# I-GAUGE_5V_Rev2.net
KiCad netlist of a schematic drawn in EAGLE
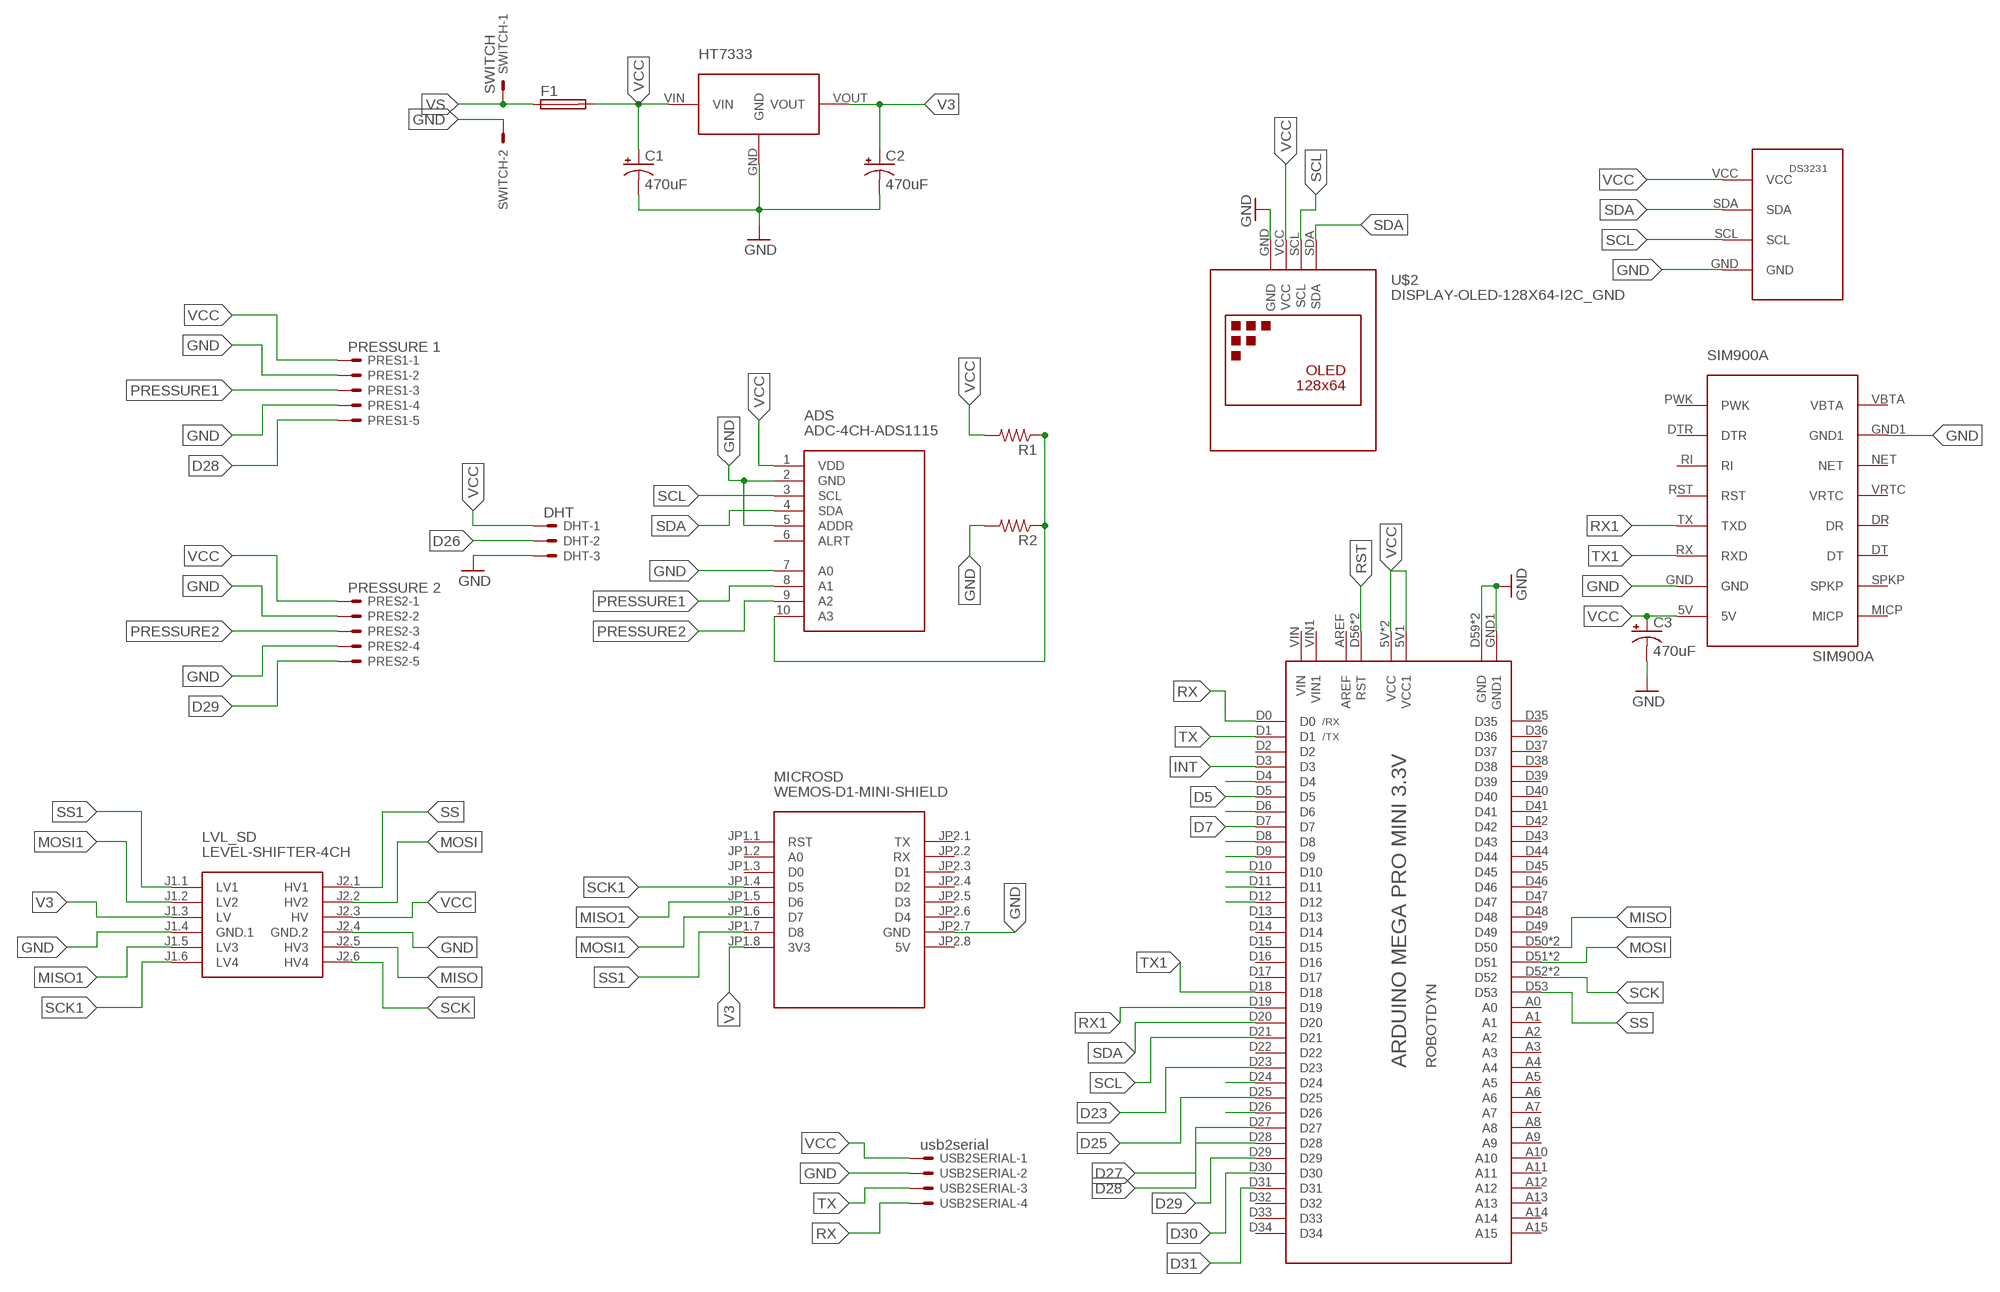
[diagram p0: schematic, sheet 1]

(export (version "E")
  (design (tool "Eeschema 10.0.6"))
  (components
    (comp (ref "ADS")
      (value "ADC-4CH-ADS1115")
      (footprint "eagle-import:ADC-4CH-ADS1115")
      (libsource (lib "eagle-import") (part "ADC-4CH-ADS1115"))
    )
    (comp (ref "C1")
      (value "470uF")
      (footprint "eagle-import:PANASONIC_G")
      (libsource (lib "eagle-import") (part "560UF-PANASONIC_G-25V-20%"))
    )
    (comp (ref "C2")
      (value "470uF")
      (footprint "eagle-import:PANASONIC_G")
      (libsource (lib "eagle-import") (part "560UF-PANASONIC_G-25V-20%"))
    )
    (comp (ref "C3")
      (value "470uF")
      (footprint "eagle-import:PANASONIC_G")
      (libsource (lib "eagle-import") (part "560UF-PANASONIC_G-25V-20%"))
    )
    (comp (ref "DHT")
      (value "DHT")
      (footprint "eagle-import:JST-XH-03-PACKAGE-ROUND-PAD")
      (libsource (lib "eagle-import") (part "JST-XH-03-PIN-ROUND-PAD"))
    )
    (comp (ref "F1")
      (value "FUSESH22,5")
      (footprint "eagle-import:SH22,5")
      (libsource (lib "eagle-import") (part "FUSESH22,5"))
    )
    (comp (ref "HT7333")
      (value "HT7333")
      (footprint "eagle-import:SOT89")
      (libsource (lib "eagle-import") (part "HT7333"))
    )
    (comp (ref "LVL_SD")
      (value "LEVEL-SHIFTER-4CH")
      (footprint "eagle-import:LEVEL-SHIFTER-4CH")
      (libsource (lib "eagle-import") (part "LEVEL-SHIFTER-4CH"))
    )
    (comp (ref "MICROSD")
      (value "WEMOS-D1-MINI-SHIELD")
      (footprint "eagle-import:WEMOS-D1-MINI-SHIELD")
      (libsource (lib "eagle-import") (part "WEMOS-D1-MINI-SHIELD"))
    )
    (comp (ref "PRES1")
      (value "PRESSURE 1")
      (footprint "eagle-import:JST-XH-05-PACKAGE-ROUND-PAD")
      (libsource (lib "eagle-import") (part "JST-XH-05-PIN-ROUND-PAD"))
    )
    (comp (ref "PRES2")
      (value "PRESSURE 2")
      (footprint "eagle-import:JST-XH-05-PACKAGE-ROUND-PAD")
      (libsource (lib "eagle-import") (part "JST-XH-05-PIN-ROUND-PAD"))
    )
    (comp (ref "R1")
      (value "R-US_M1206")
      (footprint "eagle-import:M1206")
      (libsource (lib "eagle-import") (part "R-US_M1206"))
    )
    (comp (ref "R2")
      (value "R-US_M1206")
      (footprint "eagle-import:M1206")
      (libsource (lib "eagle-import") (part "R-US_M1206"))
    )
    (comp (ref "SWITCH")
      (value "SWITCH")
      (footprint "eagle-import:JST-XH-02-PACKAGE-ROUND-PAD")
      (libsource (lib "eagle-import") (part "JST-XH-02-PIN-ROUND-PAD"))
    )
    (comp (ref "U$1")
      (value "MEGA-PRO-MINI")
      (footprint "eagle-import:MEGA-PRO-MINI")
      (libsource (lib "eagle-import") (part "MEGA-PRO-MINI"))
    )
    (comp (ref "U$2")
      (value "DISPLAY-OLED-128X64-I2C_GND")
      (footprint "eagle-import:DISPLAY-OLED-128X64-I2C_GND")
      (libsource (lib "eagle-import") (part "DISPLAY-OLED-128X64-I2C_GND"))
    )
    (comp (ref "U$5")
      (value "DS3231_RASP")
      (footprint "eagle-import:DS3231_RASP")
      (libsource (lib "eagle-import") (part "DS3231_RASP"))
    )
    (comp (ref "U$6")
      (value "SIM900A")
      (footprint "eagle-import:SIM900A")
      (libsource (lib "eagle-import") (part "SIM900A"))
    )
    (comp (ref "USB2SERIAL")
      (value "usb2serial")
      (footprint "eagle-import:JST-XH-04-PACKAGE-ROUND-PAD")
      (libsource (lib "eagle-import") (part "JST-XH-04-PIN-ROUND-PAD"))
    )
  )
  (nets
    (net (code "1") (name "/5V") (class "Default")
      (node (ref "MICROSD") (pin "JP2.8") (pinfunction "5V_JP2.8") (pintype "power_in"))
    )
    (net (code "2") (name "D5") (class "Default")
      (node (ref "U$1") (pin "D5") (pinfunction "D5_D5") (pintype "bidirectional"))
    )
    (net (code "3") (name "D7") (class "Default")
      (node (ref "U$1") (pin "D7") (pinfunction "D7_D7") (pintype "bidirectional"))
    )
    (net (code "4") (name "D23") (class "Default")
      (node (ref "U$1") (pin "D23") (pinfunction "D23_D23") (pintype "bidirectional"))
    )
    (net (code "5") (name "D25") (class "Default")
      (node (ref "U$1") (pin "D25") (pinfunction "D25_D25") (pintype "bidirectional"))
    )
    (net (code "6") (name "D26") (class "Default")
      (node (ref "DHT") (pin "2") (pinfunction "S_2") (pintype "passive"))
      (node (ref "U$1") (pin "D26") (pinfunction "D26_D26") (pintype "bidirectional"))
    )
    (net (code "7") (name "D27") (class "Default")
      (node (ref "U$1") (pin "D27") (pinfunction "D27_D27") (pintype "bidirectional"))
    )
    (net (code "8") (name "D28") (class "Default")
      (node (ref "PRES1") (pin "5") (pinfunction "S_5") (pintype "passive"))
      (node (ref "U$1") (pin "D28") (pinfunction "D28_D28") (pintype "bidirectional"))
    )
    (net (code "9") (name "D29") (class "Default")
      (node (ref "PRES2") (pin "5") (pinfunction "S_5") (pintype "passive"))
      (node (ref "U$1") (pin "D29") (pinfunction "D29_D29") (pintype "bidirectional"))
    )
    (net (code "10") (name "D30") (class "Default")
      (node (ref "U$1") (pin "D30") (pinfunction "D30_D30") (pintype "bidirectional"))
    )
    (net (code "11") (name "D31") (class "Default")
      (node (ref "U$1") (pin "D31") (pinfunction "D31_D31") (pintype "bidirectional"))
    )
    (net (code "12") (name "GND") (class "Default")
      (node (ref "ADS") (pin "2") (pinfunction "GND_2") (pintype "power_in"))
      (node (ref "ADS") (pin "5") (pinfunction "ADDR_5") (pintype "bidirectional"))
      (node (ref "ADS") (pin "7") (pinfunction "A0_7") (pintype "input"))
      (node (ref "C1") (pin "-") (pinfunction "-_-") (pintype "passive"))
      (node (ref "C2") (pin "-") (pinfunction "-_-") (pintype "passive"))
      (node (ref "C3") (pin "-") (pinfunction "-_-") (pintype "passive"))
      (node (ref "DHT") (pin "3") (pinfunction "S_3") (pintype "passive"))
      (node (ref "HT7333") (pin "GND") (pinfunction "GND_GND") (pintype "bidirectional"))
      (node (ref "LVL_SD") (pin "J1.4") (pinfunction "GND.1_J1.4") (pintype "power_in"))
      (node (ref "LVL_SD") (pin "J2.4") (pinfunction "GND.2_J2.4") (pintype "power_in"))
      (node (ref "MICROSD") (pin "JP2.7") (pinfunction "GND_JP2.7") (pintype "power_in"))
      (node (ref "PRES1") (pin "2") (pinfunction "S_2") (pintype "passive"))
      (node (ref "PRES1") (pin "4") (pinfunction "S_4") (pintype "passive"))
      (node (ref "PRES2") (pin "2") (pinfunction "S_2") (pintype "passive"))
      (node (ref "PRES2") (pin "4") (pinfunction "S_4") (pintype "passive"))
      (node (ref "R2") (pin "2") (pinfunction "2_2") (pintype "passive"))
      (node (ref "SWITCH") (pin "2") (pinfunction "S_2") (pintype "passive"))
      (node (ref "U$1") (pin "D59") (pinfunction "GND_D59") (pintype "bidirectional"))
      (node (ref "U$1") (pin "GND") (pinfunction "GND_GND") (pintype "bidirectional"))
      (node (ref "U$1") (pin "GND1") (pinfunction "GND1_GND1") (pintype "bidirectional"))
      (node (ref "U$2") (pin "GND") (pinfunction "GND_GND") (pintype "power_in"))
      (node (ref "U$5") (pin "GND") (pinfunction "GND_GND") (pintype "bidirectional"))
      (node (ref "U$6") (pin "GND") (pinfunction "GND_GND") (pintype "bidirectional"))
      (node (ref "U$6") (pin "GND1") (pinfunction "GND1_GND1") (pintype "bidirectional"))
      (node (ref "USB2SERIAL") (pin "2") (pinfunction "S_2") (pintype "passive"))
    )
    (net (code "13") (name "INT") (class "Default")
      (node (ref "U$1") (pin "D3") (pinfunction "D3_D3") (pintype "bidirectional"))
    )
    (net (code "14") (name "MISO") (class "Default")
      (node (ref "LVL_SD") (pin "J2.5") (pinfunction "HV3_J2.5") (pintype "bidirectional"))
      (node (ref "U$1") (pin "D50") (pinfunction "D50_D50") (pintype "bidirectional"))
      (node (ref "U$1") (pin "D54") (pinfunction "D50_D54") (pintype "bidirectional"))
    )
    (net (code "15") (name "MISO1") (class "Default")
      (node (ref "LVL_SD") (pin "J1.5") (pinfunction "LV3_J1.5") (pintype "bidirectional"))
      (node (ref "MICROSD") (pin "JP1.5") (pinfunction "D6_JP1.5") (pintype "bidirectional"))
    )
    (net (code "16") (name "MOSI") (class "Default")
      (node (ref "LVL_SD") (pin "J2.2") (pinfunction "HV2_J2.2") (pintype "bidirectional"))
      (node (ref "U$1") (pin "D51") (pinfunction "D51_D51") (pintype "bidirectional"))
      (node (ref "U$1") (pin "D58") (pinfunction "D51_D58") (pintype "bidirectional"))
    )
    (net (code "17") (name "MOSI1") (class "Default")
      (node (ref "LVL_SD") (pin "J1.2") (pinfunction "LV2_J1.2") (pintype "bidirectional"))
      (node (ref "MICROSD") (pin "JP1.6") (pinfunction "D7_JP1.6") (pintype "bidirectional"))
    )
    (net (code "18") (name "PRESSURE1") (class "Default")
      (node (ref "ADS") (pin "8") (pinfunction "A1_8") (pintype "input"))
      (node (ref "PRES1") (pin "3") (pinfunction "S_3") (pintype "passive"))
    )
    (net (code "19") (name "PRESSURE2") (class "Default")
      (node (ref "ADS") (pin "9") (pinfunction "A2_9") (pintype "input"))
      (node (ref "PRES2") (pin "3") (pinfunction "S_3") (pintype "passive"))
    )
    (net (code "20") (name "RST") (class "Default")
      (node (ref "U$1") (pin "D56") (pinfunction "RST_D56") (pintype "bidirectional"))
      (node (ref "U$1") (pin "RST") (pinfunction "RST_RST") (pintype "bidirectional"))
    )
    (net (code "21") (name "RX") (class "Default")
      (node (ref "U$1") (pin "D0") (pinfunction "D0_D0") (pintype "bidirectional"))
      (node (ref "USB2SERIAL") (pin "4") (pinfunction "S_4") (pintype "passive"))
    )
    (net (code "22") (name "RX1") (class "Default")
      (node (ref "U$1") (pin "D19") (pinfunction "D19_D19") (pintype "bidirectional"))
      (node (ref "U$6") (pin "TX") (pinfunction "TXD_TX") (pintype "bidirectional"))
    )
    (net (code "23") (name "SCK") (class "Default")
      (node (ref "LVL_SD") (pin "J2.6") (pinfunction "HV4_J2.6") (pintype "bidirectional"))
      (node (ref "U$1") (pin "D52") (pinfunction "D52_D52") (pintype "bidirectional"))
      (node (ref "U$1") (pin "D55") (pinfunction "D52_D55") (pintype "bidirectional"))
    )
    (net (code "24") (name "SCK1") (class "Default")
      (node (ref "LVL_SD") (pin "J1.6") (pinfunction "LV4_J1.6") (pintype "bidirectional"))
      (node (ref "MICROSD") (pin "JP1.4") (pinfunction "D5_JP1.4") (pintype "bidirectional"))
    )
    (net (code "25") (name "SCL") (class "Default")
      (node (ref "ADS") (pin "3") (pinfunction "SCL_3") (pintype "bidirectional"))
      (node (ref "U$1") (pin "D21") (pinfunction "D21_D21") (pintype "bidirectional"))
      (node (ref "U$2") (pin "SCL") (pinfunction "SCL_SCL") (pintype "bidirectional"))
      (node (ref "U$5") (pin "SCL") (pinfunction "SCL_SCL") (pintype "bidirectional"))
    )
    (net (code "26") (name "SDA") (class "Default")
      (node (ref "ADS") (pin "4") (pinfunction "SDA_4") (pintype "bidirectional"))
      (node (ref "U$1") (pin "D20") (pinfunction "D20_D20") (pintype "bidirectional"))
      (node (ref "U$2") (pin "SDA") (pinfunction "SDA_SDA") (pintype "bidirectional"))
      (node (ref "U$5") (pin "SDA") (pinfunction "SDA_SDA") (pintype "bidirectional"))
    )
    (net (code "27") (name "SS") (class "Default")
      (node (ref "LVL_SD") (pin "J2.1") (pinfunction "HV1_J2.1") (pintype "bidirectional"))
      (node (ref "U$1") (pin "D53") (pinfunction "D53_D53") (pintype "bidirectional"))
    )
    (net (code "28") (name "SS1") (class "Default")
      (node (ref "LVL_SD") (pin "J1.1") (pinfunction "LV1_J1.1") (pintype "bidirectional"))
      (node (ref "MICROSD") (pin "JP1.7") (pinfunction "D8_JP1.7") (pintype "bidirectional"))
    )
    (net (code "29") (name "TX") (class "Default")
      (node (ref "U$1") (pin "D1") (pinfunction "D1_D1") (pintype "bidirectional"))
      (node (ref "USB2SERIAL") (pin "3") (pinfunction "S_3") (pintype "passive"))
    )
    (net (code "30") (name "TX1") (class "Default")
      (node (ref "U$1") (pin "D18") (pinfunction "D18_D18") (pintype "bidirectional"))
      (node (ref "U$6") (pin "RX") (pinfunction "RXD_RX") (pintype "bidirectional"))
    )
    (net (code "31") (name "V3") (class "Default")
      (node (ref "C2") (pin "+") (pinfunction "+_+") (pintype "passive"))
      (node (ref "HT7333") (pin "VOUT") (pinfunction "VOUT_VOUT") (pintype "bidirectional"))
      (node (ref "LVL_SD") (pin "J1.3") (pinfunction "LV_J1.3") (pintype "power_in"))
      (node (ref "MICROSD") (pin "JP1.8") (pinfunction "3V3_JP1.8") (pintype "power_in"))
    )
    (net (code "32") (name "VCC") (class "Default")
      (node (ref "ADS") (pin "1") (pinfunction "VDD_1") (pintype "power_in"))
      (node (ref "ADS") (pin "10") (pinfunction "A3_10") (pintype "input"))
      (node (ref "C1") (pin "+") (pinfunction "+_+") (pintype "passive"))
      (node (ref "C3") (pin "+") (pinfunction "+_+") (pintype "passive"))
      (node (ref "DHT") (pin "1") (pinfunction "S_1") (pintype "passive"))
      (node (ref "F1") (pin "2") (pinfunction "2_2") (pintype "passive"))
      (node (ref "HT7333") (pin "VIN") (pinfunction "VIN_VIN") (pintype "bidirectional"))
      (node (ref "LVL_SD") (pin "J2.3") (pinfunction "HV_J2.3") (pintype "power_in"))
      (node (ref "PRES1") (pin "1") (pinfunction "S_1") (pintype "passive"))
      (node (ref "PRES2") (pin "1") (pinfunction "S_1") (pintype "passive"))
      (node (ref "R1") (pin "1") (pinfunction "1_1") (pintype "passive"))
      (node (ref "R1") (pin "2") (pinfunction "2_2") (pintype "passive"))
      (node (ref "R2") (pin "1") (pinfunction "1_1") (pintype "passive"))
      (node (ref "U$1") (pin "5V") (pinfunction "VCC_5V") (pintype "bidirectional"))
      (node (ref "U$1") (pin "5V1") (pinfunction "VCC1_5V1") (pintype "bidirectional"))
      (node (ref "U$1") (pin "D57") (pinfunction "VCC_D57") (pintype "bidirectional"))
      (node (ref "U$2") (pin "VCC") (pinfunction "VCC_VCC") (pintype "power_in"))
      (node (ref "U$5") (pin "VCC") (pinfunction "VCC_VCC") (pintype "bidirectional"))
      (node (ref "U$6") (pin "5V") (pinfunction "5V_5V") (pintype "bidirectional"))
      (node (ref "USB2SERIAL") (pin "1") (pinfunction "S_1") (pintype "passive"))
    )
    (net (code "33") (name "VS") (class "Default")
      (node (ref "F1") (pin "1") (pinfunction "1_1") (pintype "passive"))
      (node (ref "SWITCH") (pin "1") (pinfunction "S_1") (pintype "passive"))
    )
    (net (code "34") (name "unconnected-(ADS-ALRT-Pad6)") (class "Default")
      (node (ref "ADS") (pin "6") (pinfunction "ALRT_6") (pintype "bidirectional"))
    )
    (net (code "35") (name "unconnected-(MICROSD-A0-PadJP1.2)") (class "Default")
      (node (ref "MICROSD") (pin "JP1.2") (pinfunction "A0_JP1.2") (pintype "bidirectional"))
    )
    (net (code "36") (name "unconnected-(MICROSD-D0-PadJP1.3)") (class "Default")
      (node (ref "MICROSD") (pin "JP1.3") (pinfunction "D0_JP1.3") (pintype "bidirectional"))
    )
    (net (code "37") (name "unconnected-(MICROSD-D1-PadJP2.3)") (class "Default")
      (node (ref "MICROSD") (pin "JP2.3") (pinfunction "D1_JP2.3") (pintype "bidirectional"))
    )
    (net (code "38") (name "unconnected-(MICROSD-D2-PadJP2.4)") (class "Default")
      (node (ref "MICROSD") (pin "JP2.4") (pinfunction "D2_JP2.4") (pintype "bidirectional"))
    )
    (net (code "39") (name "unconnected-(MICROSD-D3-PadJP2.5)") (class "Default")
      (node (ref "MICROSD") (pin "JP2.5") (pinfunction "D3_JP2.5") (pintype "bidirectional"))
    )
    (net (code "40") (name "unconnected-(MICROSD-D4-PadJP2.6)") (class "Default")
      (node (ref "MICROSD") (pin "JP2.6") (pinfunction "D4_JP2.6") (pintype "bidirectional"))
    )
    (net (code "41") (name "unconnected-(MICROSD-RST-PadJP1.1)") (class "Default")
      (node (ref "MICROSD") (pin "JP1.1") (pinfunction "RST_JP1.1") (pintype "bidirectional"))
    )
    (net (code "42") (name "unconnected-(MICROSD-RX-PadJP2.2)") (class "Default")
      (node (ref "MICROSD") (pin "JP2.2") (pinfunction "RX_JP2.2") (pintype "bidirectional"))
    )
    (net (code "43") (name "unconnected-(MICROSD-TX-PadJP2.1)") (class "Default")
      (node (ref "MICROSD") (pin "JP2.1") (pinfunction "TX_JP2.1") (pintype "bidirectional"))
    )
    (net (code "44") (name "unconnected-(U$1-PadA0)") (class "Default")
      (node (ref "U$1") (pin "A0") (pinfunction "A0_A0") (pintype "bidirectional"))
    )
    (net (code "45") (name "unconnected-(U$1-PadA1)") (class "Default")
      (node (ref "U$1") (pin "A1") (pinfunction "A1_A1") (pintype "bidirectional"))
    )
    (net (code "46") (name "unconnected-(U$1-PadA2)") (class "Default")
      (node (ref "U$1") (pin "A2") (pinfunction "A2_A2") (pintype "bidirectional"))
    )
    (net (code "47") (name "unconnected-(U$1-PadA3)") (class "Default")
      (node (ref "U$1") (pin "A3") (pinfunction "A3_A3") (pintype "bidirectional"))
    )
    (net (code "48") (name "unconnected-(U$1-PadA4)") (class "Default")
      (node (ref "U$1") (pin "A4") (pinfunction "A4_A4") (pintype "bidirectional"))
    )
    (net (code "49") (name "unconnected-(U$1-PadA5)") (class "Default")
      (node (ref "U$1") (pin "A5") (pinfunction "A5_A5") (pintype "bidirectional"))
    )
    (net (code "50") (name "unconnected-(U$1-PadA6)") (class "Default")
      (node (ref "U$1") (pin "A6") (pinfunction "A6_A6") (pintype "bidirectional"))
    )
    (net (code "51") (name "unconnected-(U$1-PadA7)") (class "Default")
      (node (ref "U$1") (pin "A7") (pinfunction "A7_A7") (pintype "bidirectional"))
    )
    (net (code "52") (name "unconnected-(U$1-PadA8)") (class "Default")
      (node (ref "U$1") (pin "A8") (pinfunction "A8_A8") (pintype "bidirectional"))
    )
    (net (code "53") (name "unconnected-(U$1-PadA9)") (class "Default")
      (node (ref "U$1") (pin "A9") (pinfunction "A9_A9") (pintype "bidirectional"))
    )
    (net (code "54") (name "unconnected-(U$1-PadA10)") (class "Default")
      (node (ref "U$1") (pin "A10") (pinfunction "A10_A10") (pintype "bidirectional"))
    )
    (net (code "55") (name "unconnected-(U$1-PadA11)") (class "Default")
      (node (ref "U$1") (pin "A11") (pinfunction "A11_A11") (pintype "bidirectional"))
    )
    (net (code "56") (name "unconnected-(U$1-PadA12)") (class "Default")
      (node (ref "U$1") (pin "A12") (pinfunction "A12_A12") (pintype "bidirectional"))
    )
    (net (code "57") (name "unconnected-(U$1-PadA13)") (class "Default")
      (node (ref "U$1") (pin "A13") (pinfunction "A13_A13") (pintype "bidirectional"))
    )
    (net (code "58") (name "unconnected-(U$1-PadA14)") (class "Default")
      (node (ref "U$1") (pin "A14") (pinfunction "A14_A14") (pintype "bidirectional"))
    )
    (net (code "59") (name "unconnected-(U$1-PadA15)") (class "Default")
      (node (ref "U$1") (pin "A15") (pinfunction "A15_A15") (pintype "bidirectional"))
    )
    (net (code "60") (name "unconnected-(U$1-PadAREF)") (class "Default")
      (node (ref "U$1") (pin "AREF") (pinfunction "AREF_AREF") (pintype "bidirectional"))
    )
    (net (code "61") (name "unconnected-(U$1-PadD2)") (class "Default")
      (node (ref "U$1") (pin "D2") (pinfunction "D2_D2") (pintype "bidirectional"))
    )
    (net (code "62") (name "unconnected-(U$1-PadD4)") (class "Default")
      (node (ref "U$1") (pin "D4") (pinfunction "D4_D4") (pintype "bidirectional"))
    )
    (net (code "63") (name "unconnected-(U$1-PadD6)") (class "Default")
      (node (ref "U$1") (pin "D6") (pinfunction "D6_D6") (pintype "bidirectional"))
    )
    (net (code "64") (name "unconnected-(U$1-PadD8)") (class "Default")
      (node (ref "U$1") (pin "D8") (pinfunction "D8_D8") (pintype "bidirectional"))
    )
    (net (code "65") (name "unconnected-(U$1-PadD9)") (class "Default")
      (node (ref "U$1") (pin "D9") (pinfunction "D9_D9") (pintype "bidirectional"))
    )
    (net (code "66") (name "unconnected-(U$1-PadD10)") (class "Default")
      (node (ref "U$1") (pin "D10") (pinfunction "D10_D10") (pintype "bidirectional"))
    )
    (net (code "67") (name "unconnected-(U$1-PadD11)") (class "Default")
      (node (ref "U$1") (pin "D11") (pinfunction "D11_D11") (pintype "bidirectional"))
    )
    (net (code "68") (name "unconnected-(U$1-PadD12)") (class "Default")
      (node (ref "U$1") (pin "D12") (pinfunction "D12_D12") (pintype "bidirectional"))
    )
    (net (code "69") (name "unconnected-(U$1-PadD13)") (class "Default")
      (node (ref "U$1") (pin "D13") (pinfunction "D13_D13") (pintype "bidirectional"))
    )
    (net (code "70") (name "unconnected-(U$1-PadD14)") (class "Default")
      (node (ref "U$1") (pin "D14") (pinfunction "D14_D14") (pintype "bidirectional"))
    )
    (net (code "71") (name "unconnected-(U$1-PadD15)") (class "Default")
      (node (ref "U$1") (pin "D15") (pinfunction "D15_D15") (pintype "bidirectional"))
    )
    (net (code "72") (name "unconnected-(U$1-PadD16)") (class "Default")
      (node (ref "U$1") (pin "D16") (pinfunction "D16_D16") (pintype "bidirectional"))
    )
    (net (code "73") (name "unconnected-(U$1-PadD17)") (class "Default")
      (node (ref "U$1") (pin "D17") (pinfunction "D17_D17") (pintype "bidirectional"))
    )
    (net (code "74") (name "unconnected-(U$1-PadD22)") (class "Default")
      (node (ref "U$1") (pin "D22") (pinfunction "D22_D22") (pintype "bidirectional"))
    )
    (net (code "75") (name "unconnected-(U$1-PadD24)") (class "Default")
      (node (ref "U$1") (pin "D24") (pinfunction "D24_D24") (pintype "bidirectional"))
    )
    (net (code "76") (name "unconnected-(U$1-PadD32)") (class "Default")
      (node (ref "U$1") (pin "D32") (pinfunction "D32_D32") (pintype "bidirectional"))
    )
    (net (code "77") (name "unconnected-(U$1-PadD33)") (class "Default")
      (node (ref "U$1") (pin "D33") (pinfunction "D33_D33") (pintype "bidirectional"))
    )
    (net (code "78") (name "unconnected-(U$1-PadD34)") (class "Default")
      (node (ref "U$1") (pin "D34") (pinfunction "D34_D34") (pintype "bidirectional"))
    )
    (net (code "79") (name "unconnected-(U$1-PadD35)") (class "Default")
      (node (ref "U$1") (pin "D35") (pinfunction "D35_D35") (pintype "bidirectional"))
    )
    (net (code "80") (name "unconnected-(U$1-PadD36)") (class "Default")
      (node (ref "U$1") (pin "D36") (pinfunction "D36_D36") (pintype "bidirectional"))
    )
    (net (code "81") (name "unconnected-(U$1-PadD37)") (class "Default")
      (node (ref "U$1") (pin "D37") (pinfunction "D37_D37") (pintype "bidirectional"))
    )
    (net (code "82") (name "unconnected-(U$1-PadD38)") (class "Default")
      (node (ref "U$1") (pin "D38") (pinfunction "D38_D38") (pintype "bidirectional"))
    )
    (net (code "83") (name "unconnected-(U$1-PadD39)") (class "Default")
      (node (ref "U$1") (pin "D39") (pinfunction "D39_D39") (pintype "bidirectional"))
    )
    (net (code "84") (name "unconnected-(U$1-PadD40)") (class "Default")
      (node (ref "U$1") (pin "D40") (pinfunction "D40_D40") (pintype "bidirectional"))
    )
    (net (code "85") (name "unconnected-(U$1-PadD41)") (class "Default")
      (node (ref "U$1") (pin "D41") (pinfunction "D41_D41") (pintype "bidirectional"))
    )
    (net (code "86") (name "unconnected-(U$1-PadD42)") (class "Default")
      (node (ref "U$1") (pin "D42") (pinfunction "D42_D42") (pintype "bidirectional"))
    )
    (net (code "87") (name "unconnected-(U$1-PadD43)") (class "Default")
      (node (ref "U$1") (pin "D43") (pinfunction "D43_D43") (pintype "bidirectional"))
    )
    (net (code "88") (name "unconnected-(U$1-PadD44)") (class "Default")
      (node (ref "U$1") (pin "D44") (pinfunction "D44_D44") (pintype "bidirectional"))
    )
    (net (code "89") (name "unconnected-(U$1-PadD45)") (class "Default")
      (node (ref "U$1") (pin "D45") (pinfunction "D45_D45") (pintype "bidirectional"))
    )
    (net (code "90") (name "unconnected-(U$1-PadD46)") (class "Default")
      (node (ref "U$1") (pin "D46") (pinfunction "D46_D46") (pintype "bidirectional"))
    )
    (net (code "91") (name "unconnected-(U$1-PadD47)") (class "Default")
      (node (ref "U$1") (pin "D47") (pinfunction "D47_D47") (pintype "bidirectional"))
    )
    (net (code "92") (name "unconnected-(U$1-PadD48)") (class "Default")
      (node (ref "U$1") (pin "D48") (pinfunction "D48_D48") (pintype "bidirectional"))
    )
    (net (code "93") (name "unconnected-(U$1-PadD49)") (class "Default")
      (node (ref "U$1") (pin "D49") (pinfunction "D49_D49") (pintype "bidirectional"))
    )
    (net (code "94") (name "unconnected-(U$1-PadVIN)") (class "Default")
      (node (ref "U$1") (pin "VIN") (pinfunction "VIN_VIN") (pintype "bidirectional"))
    )
    (net (code "95") (name "unconnected-(U$1-PadVIN1)") (class "Default")
      (node (ref "U$1") (pin "VIN1") (pinfunction "VIN1_VIN1") (pintype "bidirectional"))
    )
    (net (code "96") (name "unconnected-(U$6-PadDR)") (class "Default")
      (node (ref "U$6") (pin "DR") (pinfunction "DR_DR") (pintype "bidirectional"))
    )
    (net (code "97") (name "unconnected-(U$6-PadDT)") (class "Default")
      (node (ref "U$6") (pin "DT") (pinfunction "DT_DT") (pintype "bidirectional"))
    )
    (net (code "98") (name "unconnected-(U$6-PadDTR)") (class "Default")
      (node (ref "U$6") (pin "DTR") (pinfunction "DTR_DTR") (pintype "bidirectional"))
    )
    (net (code "99") (name "unconnected-(U$6-PadMICP)") (class "Default")
      (node (ref "U$6") (pin "MICP") (pinfunction "MICP_MICP") (pintype "bidirectional"))
    )
    (net (code "100") (name "unconnected-(U$6-PadNET)") (class "Default")
      (node (ref "U$6") (pin "NET") (pinfunction "NET_NET") (pintype "bidirectional"))
    )
    (net (code "101") (name "unconnected-(U$6-PadPWK)") (class "Default")
      (node (ref "U$6") (pin "PWK") (pinfunction "PWK_PWK") (pintype "bidirectional"))
    )
    (net (code "102") (name "unconnected-(U$6-PadRI)") (class "Default")
      (node (ref "U$6") (pin "RI") (pinfunction "RI_RI") (pintype "bidirectional"))
    )
    (net (code "103") (name "unconnected-(U$6-PadRST)") (class "Default")
      (node (ref "U$6") (pin "RST") (pinfunction "RST_RST") (pintype "bidirectional"))
    )
    (net (code "104") (name "unconnected-(U$6-PadSPKP)") (class "Default")
      (node (ref "U$6") (pin "SPKP") (pinfunction "SPKP_SPKP") (pintype "bidirectional"))
    )
    (net (code "105") (name "unconnected-(U$6-PadVBTA)") (class "Default")
      (node (ref "U$6") (pin "VBTA") (pinfunction "VBTA_VBTA") (pintype "bidirectional"))
    )
    (net (code "106") (name "unconnected-(U$6-PadVRTC)") (class "Default")
      (node (ref "U$6") (pin "VRTC") (pinfunction "VRTC_VRTC") (pintype "bidirectional"))
    )
  )
)
